# CycleOpsPro300toANTPlus_V1_0.net
KiCad netlist of a schematic drawn in EAGLE
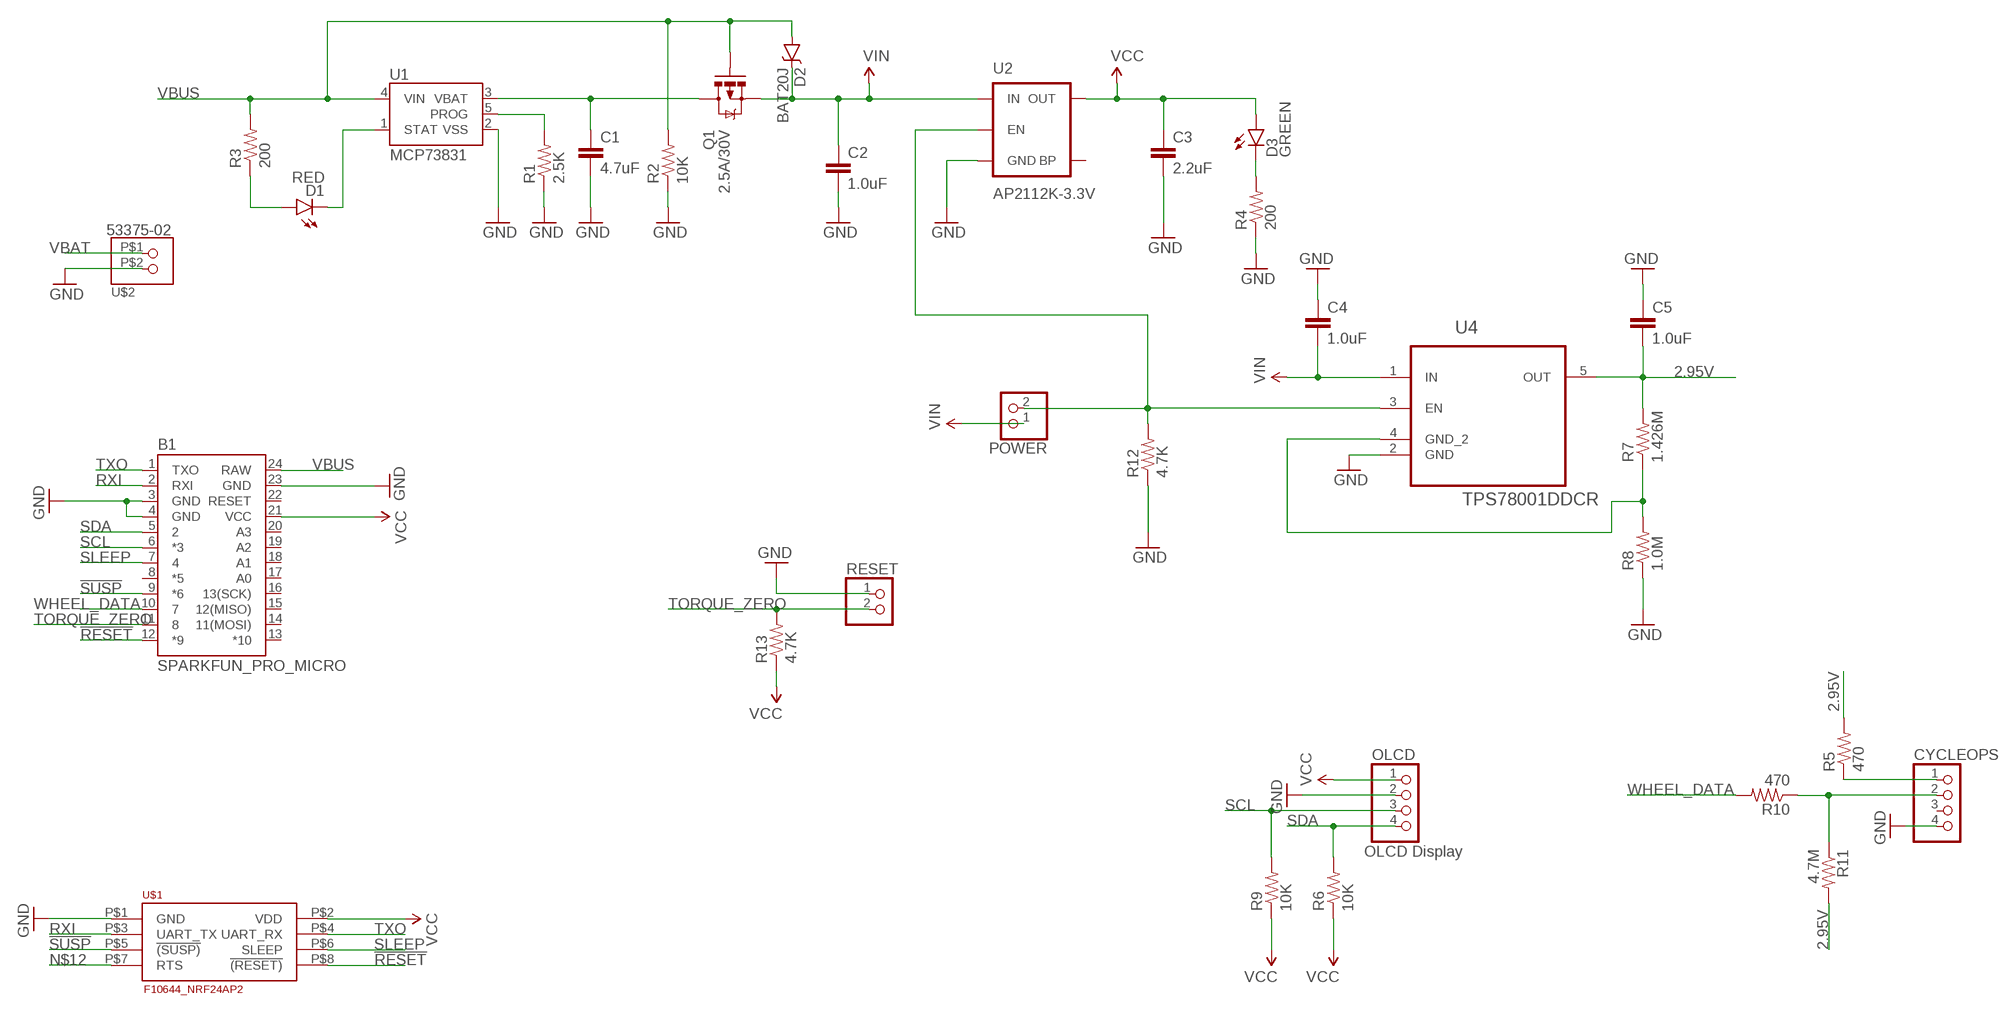
[diagram p0: schematic, sheet 1]

(export (version "E")
  (design (tool "Eeschema 10.0.6"))
  (components
    (comp (ref "B1")
      (value "SPARKFUN_PRO_MICRO")
      (footprint "eagle-import:SPARKFUN_PRO_MICRO")
      (libsource (lib "eagle-import") (part "SPARKFUN_PRO_MICRO"))
    )
    (comp (ref "C1")
      (value "4.7uF")
      (footprint "eagle-import:0603-CAP")
      (libsource (lib "eagle-import") (part "CAP0603-CAP"))
    )
    (comp (ref "C2")
      (value "1.0uF")
      (footprint "eagle-import:0603-CAP")
      (libsource (lib "eagle-import") (part "CAP0603-CAP"))
    )
    (comp (ref "C3")
      (value "2.2uF")
      (footprint "eagle-import:0603-CAP")
      (libsource (lib "eagle-import") (part "CAP0603-CAP"))
    )
    (comp (ref "C4")
      (value "1.0uF")
      (footprint "eagle-import:0603-CAP")
      (libsource (lib "eagle-import") (part "CAP0603-CAP"))
    )
    (comp (ref "C5")
      (value "1.0uF")
      (footprint "eagle-import:0603-CAP")
      (libsource (lib "eagle-import") (part "CAP0603-CAP"))
    )
    (comp (ref "CYCLEOPS")
      (value "PINHD-1X4")
      (footprint "eagle-import:1X04")
      (libsource (lib "eagle-import") (part "PINHD-1X4"))
    )
    (comp (ref "D1")
      (value "RED")
      (footprint "eagle-import:LED-0603")
      (libsource (lib "eagle-import") (part "LED0603"))
    )
    (comp (ref "D2")
      (value "BAT20J")
      (footprint "eagle-import:SOD-323")
      (libsource (lib "eagle-import") (part "DIODE-SCHOTTKY-BAT20J"))
    )
    (comp (ref "D3")
      (value "GREEN")
      (footprint "eagle-import:LED-0603")
      (libsource (lib "eagle-import") (part "LED0603"))
    )
    (comp (ref "OLCD")
      (value "PINHD-1X4")
      (footprint "eagle-import:1X04")
      (libsource (lib "eagle-import") (part "PINHD-1X4"))
    )
    (comp (ref "POWER")
      (value "PINHD-1X2")
      (footprint "eagle-import:1X02")
      (libsource (lib "eagle-import") (part "PINHD-1X2"))
    )
    (comp (ref "Q1")
      (value "2.5A/30V")
      (footprint "eagle-import:SOT23-3")
      (libsource (lib "eagle-import") (part "MOSFET-PCHANNELDMG2307L"))
    )
    (comp (ref "R1")
      (value "2.5K")
      (footprint "eagle-import:0603-RES")
      (libsource (lib "eagle-import") (part "RESISTOR0603-RES"))
    )
    (comp (ref "R2")
      (value "10K")
      (footprint "eagle-import:0603-RES")
      (libsource (lib "eagle-import") (part "RESISTOR0603-RES"))
    )
    (comp (ref "R3")
      (value "200")
      (footprint "eagle-import:0603-RES")
      (libsource (lib "eagle-import") (part "RESISTOR0603-RES"))
    )
    (comp (ref "R4")
      (value "200")
      (footprint "eagle-import:0603-RES")
      (libsource (lib "eagle-import") (part "RESISTOR0603-RES"))
    )
    (comp (ref "R5")
      (value "470")
      (footprint "eagle-import:0603-RES")
      (libsource (lib "eagle-import") (part "RESISTOR0603-RES"))
    )
    (comp (ref "R6")
      (value "10K")
      (footprint "eagle-import:0603-RES")
      (libsource (lib "eagle-import") (part "RESISTOR0603-RES"))
    )
    (comp (ref "R7")
      (value "1.426M")
      (footprint "eagle-import:0603-RES")
      (libsource (lib "eagle-import") (part "RESISTOR0603-RES"))
    )
    (comp (ref "R8")
      (value "1.0M")
      (footprint "eagle-import:0603-RES")
      (libsource (lib "eagle-import") (part "RESISTOR0603-RES"))
    )
    (comp (ref "R9")
      (value "10K")
      (footprint "eagle-import:0603-RES")
      (libsource (lib "eagle-import") (part "RESISTOR0603-RES"))
    )
    (comp (ref "R10")
      (value "470")
      (footprint "eagle-import:0603-RES")
      (libsource (lib "eagle-import") (part "RESISTOR0603-RES"))
    )
    (comp (ref "R11")
      (value "4.7M")
      (footprint "eagle-import:0603-RES")
      (libsource (lib "eagle-import") (part "RESISTOR0603-RES"))
    )
    (comp (ref "R12")
      (value "4.7K")
      (footprint "eagle-import:0603-RES")
      (libsource (lib "eagle-import") (part "RESISTOR0603-RES"))
    )
    (comp (ref "R13")
      (value "4.7K")
      (footprint "eagle-import:0603-RES")
      (libsource (lib "eagle-import") (part "RESISTOR0603-RES"))
    )
    (comp (ref "RESET")
      (value "PINHD-1X2")
      (footprint "eagle-import:1X02")
      (libsource (lib "eagle-import") (part "PINHD-1X2"))
    )
    (comp (ref "U$1")
      (value "F10644_NRF24AP2")
      (footprint "eagle-import:F10644_NRF24AP2")
      (libsource (lib "eagle-import") (part "F10644_NRF24AP2"))
    )
    (comp (ref "U$2")
      (value "53375-02")
      (footprint "eagle-import:53375-02")
      (libsource (lib "eagle-import") (part "53375-02"))
    )
    (comp (ref "U1")
      (value "MCP73831")
      (footprint "eagle-import:SOT23-5")
      (libsource (lib "eagle-import") (part "MCP73831"))
    )
    (comp (ref "U2")
      (value "AP2112K-3.3V")
      (footprint "eagle-import:SOT23-5")
      (libsource (lib "eagle-import") (part "V_REG_LDOSMD"))
    )
    (comp (ref "U4")
      (value "TPS78001DDCR")
      (footprint "eagle-import:SOT95P280X110-5N")
      (fields (field (name "MPN") "TPS78223DDCR"))
      (libsource (lib "eagle-import") (part "TPS78223DDCR"))
    )
  )
  (nets
    (net (code "1") (name "/2.95V") (class "Default")
      (node (ref "C5") (pin "2") (pinfunction "2_2") (pintype "passive"))
      (node (ref "R11") (pin "2") (pinfunction "2_2") (pintype "passive"))
      (node (ref "R5") (pin "2") (pinfunction "2_2") (pintype "passive"))
      (node (ref "R7") (pin "2") (pinfunction "2_2") (pintype "passive"))
      (node (ref "U4") (pin "5") (pinfunction "OUT_5") (pintype "output"))
    )
    (net (code "2") (name "/N$12") (class "Default")
      (node (ref "U$1") (pin "P$7") (pinfunction "RTS_P$7") (pintype "bidirectional"))
    )
    (net (code "3") (name "/RXI") (class "Default")
      (node (ref "B1") (pin "2") (pinfunction "RXI_2") (pintype "bidirectional"))
      (node (ref "U$1") (pin "P$3") (pinfunction "UART_TX_P$3") (pintype "bidirectional"))
    )
    (net (code "4") (name "/SCL") (class "Default")
      (node (ref "B1") (pin "6") (pinfunction "*3_6") (pintype "bidirectional"))
      (node (ref "OLCD") (pin "3") (pinfunction "3_3") (pintype "passive"))
      (node (ref "R9") (pin "2") (pinfunction "2_2") (pintype "passive"))
    )
    (net (code "5") (name "/SDA") (class "Default")
      (node (ref "B1") (pin "5") (pinfunction "2_5") (pintype "bidirectional"))
      (node (ref "OLCD") (pin "4") (pinfunction "4_4") (pintype "passive"))
      (node (ref "R6") (pin "2") (pinfunction "2_2") (pintype "passive"))
    )
    (net (code "6") (name "/SLEEP") (class "Default")
      (node (ref "B1") (pin "7") (pinfunction "4_7") (pintype "bidirectional"))
      (node (ref "U$1") (pin "P$6") (pinfunction "SLEEP_P$6") (pintype "bidirectional"))
    )
    (net (code "7") (name "/TORQUE_ZERO") (class "Default")
      (node (ref "B1") (pin "11") (pinfunction "8_11") (pintype "bidirectional"))
      (node (ref "R13") (pin "2") (pinfunction "2_2") (pintype "passive"))
      (node (ref "RESET") (pin "2") (pinfunction "2_2") (pintype "passive"))
    )
    (net (code "8") (name "/TXO") (class "Default")
      (node (ref "B1") (pin "1") (pinfunction "TXO_1") (pintype "bidirectional"))
      (node (ref "U$1") (pin "P$4") (pinfunction "UART_RX_P$4") (pintype "bidirectional"))
    )
    (net (code "9") (name "/VBAT") (class "Default")
      (node (ref "C1") (pin "1") (pinfunction "1_1") (pintype "passive"))
      (node (ref "Q1") (pin "3") (pinfunction "D_3") (pintype "passive"))
      (node (ref "U$2") (pin "P$1") (pinfunction "P$1_P$1") (pintype "bidirectional"))
      (node (ref "U1") (pin "3") (pinfunction "VBAT_3") (pintype "power_in"))
    )
    (net (code "10") (name "/VBUS") (class "Default")
      (node (ref "B1") (pin "24") (pinfunction "RAW_24") (pintype "power_in"))
      (node (ref "D2") (pin "A") (pinfunction "A_A") (pintype "passive"))
      (node (ref "Q1") (pin "1") (pinfunction "G_1") (pintype "passive"))
      (node (ref "R2") (pin "2") (pinfunction "2_2") (pintype "passive"))
      (node (ref "R3") (pin "2") (pinfunction "2_2") (pintype "passive"))
      (node (ref "U1") (pin "4") (pinfunction "VIN_4") (pintype "power_in"))
    )
    (net (code "11") (name "/WHEEL_DATA") (class "Default")
      (node (ref "B1") (pin "10") (pinfunction "7_10") (pintype "bidirectional"))
      (node (ref "R10") (pin "2") (pinfunction "2_2") (pintype "passive"))
    )
    (net (code "12") (name "/~{RESET}") (class "Default")
      (node (ref "B1") (pin "12") (pinfunction "*9_12") (pintype "bidirectional"))
      (node (ref "U$1") (pin "P$8") (pinfunction "~{(RESET})_P$8") (pintype "bidirectional"))
    )
    (net (code "13") (name "/~{SUSP}") (class "Default")
      (node (ref "B1") (pin "9") (pinfunction "*6_9") (pintype "bidirectional"))
      (node (ref "U$1") (pin "P$5") (pinfunction "~{(SUSP})_P$5") (pintype "bidirectional"))
    )
    (net (code "14") (name "GND") (class "Default")
      (node (ref "B1") (pin "23") (pinfunction "GND_23") (pintype "power_in"))
      (node (ref "B1") (pin "3") (pinfunction "GND_3") (pintype "power_in"))
      (node (ref "B1") (pin "4") (pinfunction "GND_4") (pintype "power_in"))
      (node (ref "C1") (pin "2") (pinfunction "2_2") (pintype "passive"))
      (node (ref "C2") (pin "2") (pinfunction "2_2") (pintype "passive"))
      (node (ref "C3") (pin "2") (pinfunction "2_2") (pintype "passive"))
      (node (ref "C4") (pin "1") (pinfunction "1_1") (pintype "passive"))
      (node (ref "C5") (pin "1") (pinfunction "1_1") (pintype "passive"))
      (node (ref "CYCLEOPS") (pin "4") (pinfunction "4_4") (pintype "passive"))
      (node (ref "OLCD") (pin "2") (pinfunction "2_2") (pintype "passive"))
      (node (ref "R1") (pin "1") (pinfunction "1_1") (pintype "passive"))
      (node (ref "R12") (pin "1") (pinfunction "1_1") (pintype "passive"))
      (node (ref "R2") (pin "1") (pinfunction "1_1") (pintype "passive"))
      (node (ref "R4") (pin "1") (pinfunction "1_1") (pintype "passive"))
      (node (ref "R8") (pin "1") (pinfunction "1_1") (pintype "passive"))
      (node (ref "RESET") (pin "1") (pinfunction "1_1") (pintype "passive"))
      (node (ref "U$1") (pin "P$1") (pinfunction "GND_P$1") (pintype "bidirectional"))
      (node (ref "U$2") (pin "P$2") (pinfunction "P$2_P$2") (pintype "bidirectional"))
      (node (ref "U1") (pin "2") (pinfunction "VSS_2") (pintype "power_in"))
      (node (ref "U2") (pin "2") (pinfunction "GND_2") (pintype "input"))
      (node (ref "U4") (pin "2") (pinfunction "GND_2") (pintype "passive"))
    )
    (net (code "15") (name "Net-(CYCLEOPS-Pad1)") (class "Default")
      (node (ref "CYCLEOPS") (pin "1") (pinfunction "1_1") (pintype "passive"))
      (node (ref "R5") (pin "1") (pinfunction "1_1") (pintype "passive"))
    )
    (net (code "16") (name "Net-(CYCLEOPS-Pad2)") (class "Default")
      (node (ref "CYCLEOPS") (pin "2") (pinfunction "2_2") (pintype "passive"))
      (node (ref "R10") (pin "1") (pinfunction "1_1") (pintype "passive"))
      (node (ref "R11") (pin "1") (pinfunction "1_1") (pintype "passive"))
    )
    (net (code "17") (name "Net-(D1-PadA)") (class "Default")
      (node (ref "D1") (pin "A") (pinfunction "A_A") (pintype "passive"))
      (node (ref "R3") (pin "1") (pinfunction "1_1") (pintype "passive"))
    )
    (net (code "18") (name "Net-(D3-PadC)") (class "Default")
      (node (ref "D3") (pin "C") (pinfunction "C_C") (pintype "passive"))
      (node (ref "R4") (pin "2") (pinfunction "2_2") (pintype "passive"))
    )
    (net (code "19") (name "Net-(U1-PROG)") (class "Default")
      (node (ref "R1") (pin "2") (pinfunction "2_2") (pintype "passive"))
      (node (ref "U1") (pin "5") (pinfunction "PROG_5") (pintype "input"))
    )
    (net (code "20") (name "Net-(U1-STAT)") (class "Default")
      (node (ref "D1") (pin "C") (pinfunction "C_C") (pintype "passive"))
      (node (ref "U1") (pin "1") (pinfunction "STAT_1") (pintype "output"))
    )
    (net (code "21") (name "Net-(U2-EN)") (class "Default")
      (node (ref "POWER") (pin "2") (pinfunction "2_2") (pintype "passive"))
      (node (ref "R12") (pin "2") (pinfunction "2_2") (pintype "passive"))
      (node (ref "U2") (pin "3") (pinfunction "EN_3") (pintype "input"))
      (node (ref "U4") (pin "3") (pinfunction "EN_3") (pintype "input"))
    )
    (net (code "22") (name "Net-(U4-GND_2)") (class "Default")
      (node (ref "R7") (pin "1") (pinfunction "1_1") (pintype "passive"))
      (node (ref "R8") (pin "2") (pinfunction "2_2") (pintype "passive"))
      (node (ref "U4") (pin "4") (pinfunction "GND_2_4") (pintype "passive"))
    )
    (net (code "23") (name "VCC") (class "Default")
      (node (ref "B1") (pin "21") (pinfunction "VCC_21") (pintype "power_in"))
      (node (ref "C3") (pin "1") (pinfunction "1_1") (pintype "passive"))
      (node (ref "D3") (pin "A") (pinfunction "A_A") (pintype "passive"))
      (node (ref "OLCD") (pin "1") (pinfunction "1_1") (pintype "passive"))
      (node (ref "R13") (pin "1") (pinfunction "1_1") (pintype "passive"))
      (node (ref "R6") (pin "1") (pinfunction "1_1") (pintype "passive"))
      (node (ref "R9") (pin "1") (pinfunction "1_1") (pintype "passive"))
      (node (ref "U$1") (pin "P$2") (pinfunction "VDD_P$2") (pintype "bidirectional"))
      (node (ref "U2") (pin "5") (pinfunction "OUT_5") (pintype "passive"))
    )
    (net (code "24") (name "VIN") (class "Default")
      (node (ref "C2") (pin "1") (pinfunction "1_1") (pintype "passive"))
      (node (ref "C4") (pin "2") (pinfunction "2_2") (pintype "passive"))
      (node (ref "D2") (pin "C") (pinfunction "C_C") (pintype "passive"))
      (node (ref "POWER") (pin "1") (pinfunction "1_1") (pintype "passive"))
      (node (ref "Q1") (pin "2") (pinfunction "S_2") (pintype "passive"))
      (node (ref "U2") (pin "1") (pinfunction "IN_1") (pintype "input"))
      (node (ref "U4") (pin "1") (pinfunction "IN_1") (pintype "input"))
    )
    (net (code "25") (name "unconnected-(B1-*5-Pad8)") (class "Default")
      (node (ref "B1") (pin "8") (pinfunction "*5_8") (pintype "bidirectional"))
    )
    (net (code "26") (name "unconnected-(B1-*10-Pad13)") (class "Default")
      (node (ref "B1") (pin "13") (pinfunction "*10_13") (pintype "bidirectional"))
    )
    (net (code "27") (name "unconnected-(B1-11(MOSI)-Pad14)") (class "Default")
      (node (ref "B1") (pin "14") (pinfunction "11(MOSI)_14") (pintype "bidirectional"))
    )
    (net (code "28") (name "unconnected-(B1-12(MISO)-Pad15)") (class "Default")
      (node (ref "B1") (pin "15") (pinfunction "12(MISO)_15") (pintype "bidirectional"))
    )
    (net (code "29") (name "unconnected-(B1-13(SCK)-Pad16)") (class "Default")
      (node (ref "B1") (pin "16") (pinfunction "13(SCK)_16") (pintype "bidirectional"))
    )
    (net (code "30") (name "unconnected-(B1-A0-Pad17)") (class "Default")
      (node (ref "B1") (pin "17") (pinfunction "A0_17") (pintype "bidirectional"))
    )
    (net (code "31") (name "unconnected-(B1-A1-Pad18)") (class "Default")
      (node (ref "B1") (pin "18") (pinfunction "A1_18") (pintype "bidirectional"))
    )
    (net (code "32") (name "unconnected-(B1-A2-Pad19)") (class "Default")
      (node (ref "B1") (pin "19") (pinfunction "A2_19") (pintype "bidirectional"))
    )
    (net (code "33") (name "unconnected-(B1-A3-Pad20)") (class "Default")
      (node (ref "B1") (pin "20") (pinfunction "A3_20") (pintype "bidirectional"))
    )
    (net (code "34") (name "unconnected-(B1-RESET-Pad22)") (class "Default")
      (node (ref "B1") (pin "22") (pinfunction "RESET_22") (pintype "bidirectional"))
    )
    (net (code "35") (name "unconnected-(CYCLEOPS-Pad3)") (class "Default")
      (node (ref "CYCLEOPS") (pin "3") (pinfunction "3_3") (pintype "passive"))
    )
    (net (code "36") (name "unconnected-(U2-BP-Pad4)") (class "Default")
      (node (ref "U2") (pin "4") (pinfunction "BP_4") (pintype "input"))
    )
  )
)
